# ETH_PCIE_PHY.net
KiCad netlist of a schematic drawn in Altium Designer
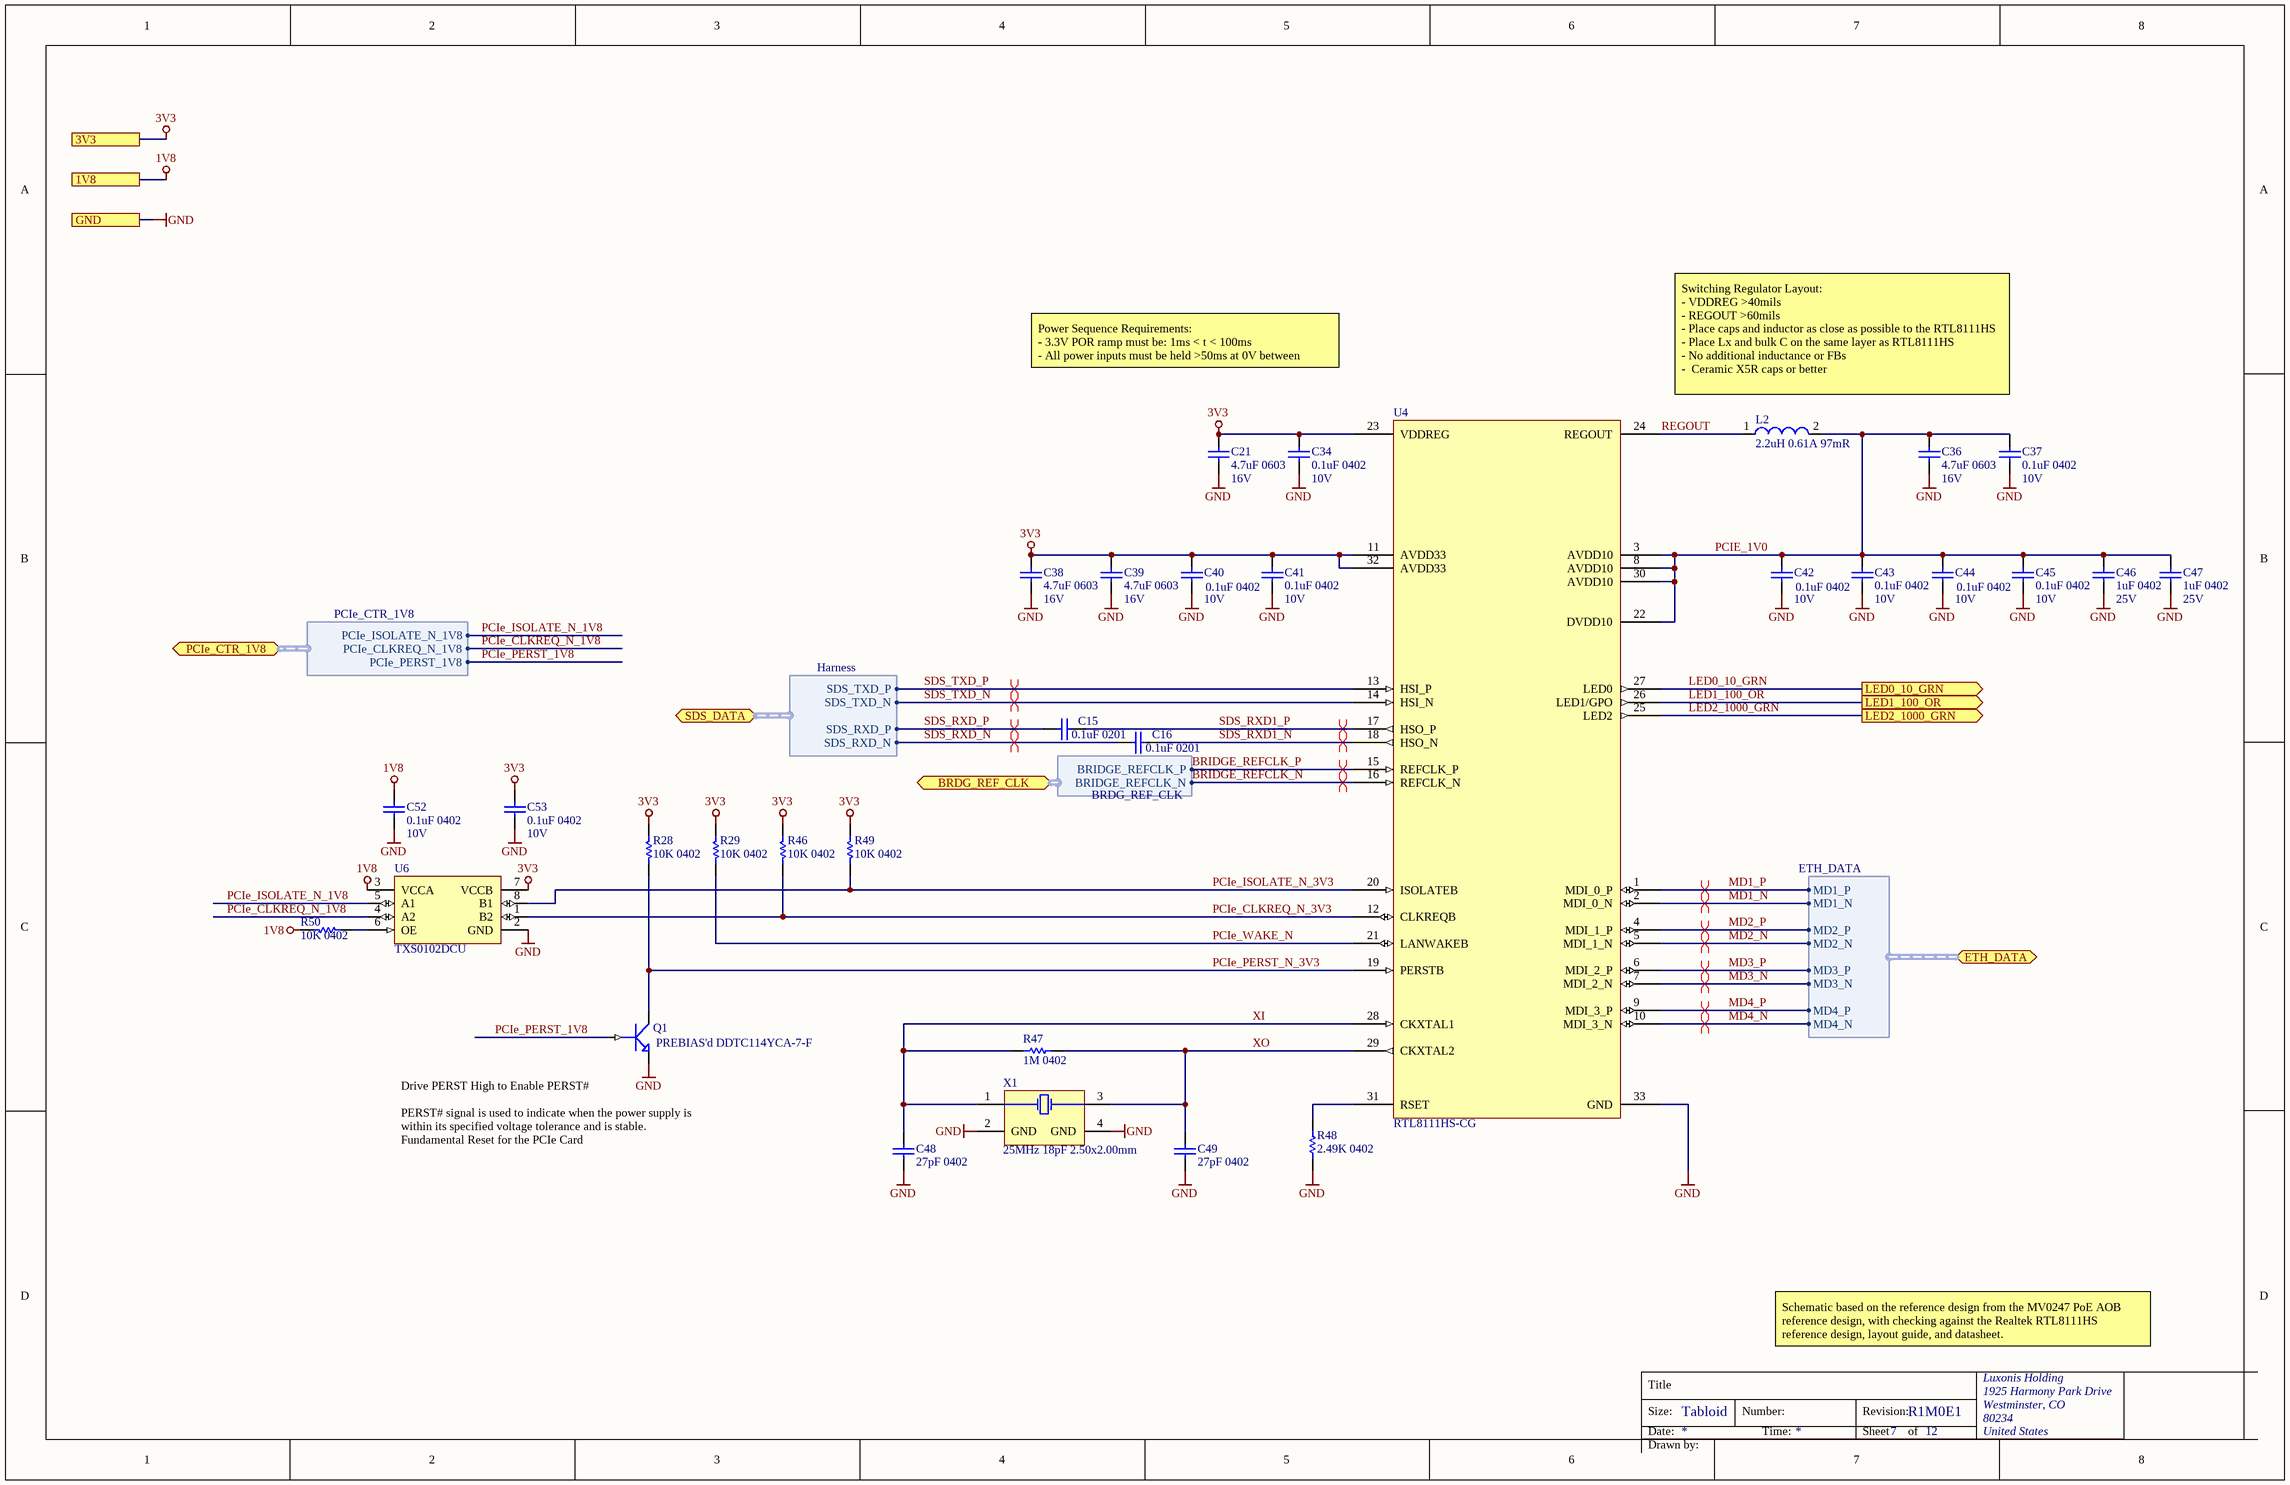
[diagram p0: ETH_PCIE_PHY.SchDoc]

(export (version "E")
  (design (tool "Eeschema 10.0.6"))
  (components
    (comp (ref "C15")
      (value "0.1uF 0201")
      (footprint "CAP_Altium_Vault_Generic:CAPC0201(0603)33_L")
      (description "CAP CER 0.1UF 10V X5R 0201")
      (fields (field (name "TOLERANCE") "10%") (field (name "VOLTAGE") "10V"))
      (libsource (lib "LuxonisMaster") (part "GRM033R61A104KE15D"))
    )
    (comp (ref "C16")
      (value "0.1uF 0201")
      (footprint "CAP_Altium_Vault_Generic:CAPC0201(0603)33_L")
      (description "CAP CER 0.1UF 10V X5R 0201")
      (fields (field (name "TOLERANCE") "10%") (field (name "VOLTAGE") "10V"))
      (libsource (lib "LuxonisMaster") (part "GRM033R61A104KE15D"))
    )
    (comp (ref "C21")
      (value "4.7uF 0603")
      (footprint "CAP_Altium_Vault_Generic:CAPC0603(1608)100_N")
      (description "CAP CER 4.7UF 16V X5R 0603 10%")
      (fields (field (name "TOLERANCE") "10%") (field (name "VOLTAGE RATING") "16V"))
      (libsource (lib "LuxonisMaster") (part "GRM188R61C475KAAJD"))
    )
    (comp (ref "C34")
      (value "0.1uF 0402")
      (footprint "CAP_Altium_Vault_Generic:CAPC0402(1005)70_N")
      (description "CAP CER 0.1UF 10V X7R 0402 5%")
      (fields (field (name "TOLERANCE") "5%") (field (name "VOLTAGE RATING") "10V"))
      (libsource (lib "LuxonisMaster") (part "GRM155R71A104JA01D"))
    )
    (comp (ref "C36")
      (value "4.7uF 0603")
      (footprint "CAP_Altium_Vault_Generic:CAPC0603(1608)100_N")
      (description "CAP CER 4.7UF 16V X5R 0603 10%")
      (fields (field (name "TOLERANCE") "10%") (field (name "VOLTAGE RATING") "16V"))
      (libsource (lib "LuxonisMaster") (part "GRM188R61C475KAAJD"))
    )
    (comp (ref "C37")
      (value "0.1uF 0402")
      (footprint "CAP_Altium_Vault_Generic:CAPC0402(1005)70_N")
      (description "CAP CER 0.1UF 10V X7R 0402 5%")
      (fields (field (name "TOLERANCE") "5%") (field (name "VOLTAGE RATING") "10V"))
      (libsource (lib "LuxonisMaster") (part "GRM155R71A104JA01D"))
    )
    (comp (ref "C38")
      (value "4.7uF 0603")
      (footprint "CAP_Altium_Vault_Generic:CAPC0603(1608)100_N")
      (description "CAP CER 4.7UF 16V X5R 0603 10%")
      (fields (field (name "TOLERANCE") "10%") (field (name "VOLTAGE RATING") "16V"))
      (libsource (lib "LuxonisMaster") (part "GRM188R61C475KAAJD"))
    )
    (comp (ref "C39")
      (value "4.7uF 0603")
      (footprint "CAP_Altium_Vault_Generic:CAPC0603(1608)100_N")
      (description "CAP CER 4.7UF 16V X5R 0603 10%")
      (fields (field (name "TOLERANCE") "10%") (field (name "VOLTAGE RATING") "16V"))
      (libsource (lib "LuxonisMaster") (part "GRM188R61C475KAAJD"))
    )
    (comp (ref "C40")
      (value "0.1uF 0402")
      (footprint "CAP_Altium_Vault_Generic:CAPC0402(1005)70_N")
      (description "CAP CER 0.1UF 10V X7R 0402 5%")
      (fields (field (name "TOLERANCE") "5%") (field (name "VOLTAGE RATING") "10V"))
      (libsource (lib "LuxonisMaster") (part "GRM155R71A104JA01D"))
    )
    (comp (ref "C41")
      (value "0.1uF 0402")
      (footprint "CAP_Altium_Vault_Generic:CAPC0402(1005)70_N")
      (description "CAP CER 0.1UF 10V X7R 0402 5%")
      (fields (field (name "TOLERANCE") "5%") (field (name "VOLTAGE RATING") "10V"))
      (libsource (lib "LuxonisMaster") (part "GRM155R71A104JA01D"))
    )
    (comp (ref "C42")
      (value "0.1uF 0402")
      (footprint "CAP_Altium_Vault_Generic:CAPC0402(1005)70_N")
      (description "CAP CER 0.1UF 10V X7R 0402 5%")
      (fields (field (name "TOLERANCE") "5%") (field (name "VOLTAGE RATING") "10V"))
      (libsource (lib "LuxonisMaster") (part "GRM155R71A104JA01D"))
    )
    (comp (ref "C43")
      (value "0.1uF 0402")
      (footprint "CAP_Altium_Vault_Generic:CAPC0402(1005)70_N")
      (description "CAP CER 0.1UF 10V X7R 0402 5%")
      (fields (field (name "TOLERANCE") "5%") (field (name "VOLTAGE RATING") "10V"))
      (libsource (lib "LuxonisMaster") (part "GRM155R71A104JA01D"))
    )
    (comp (ref "C44")
      (value "0.1uF 0402")
      (footprint "CAP_Altium_Vault_Generic:CAPC0402(1005)70_N")
      (description "CAP CER 0.1UF 10V X7R 0402 5%")
      (fields (field (name "TOLERANCE") "5%") (field (name "VOLTAGE RATING") "10V"))
      (libsource (lib "LuxonisMaster") (part "GRM155R71A104JA01D"))
    )
    (comp (ref "C45")
      (value "0.1uF 0402")
      (footprint "CAP_Altium_Vault_Generic:CAPC0402(1005)70_N")
      (description "CAP CER 0.1UF 10V X7R 0402 5%")
      (fields (field (name "TOLERANCE") "5%") (field (name "VOLTAGE RATING") "10V"))
      (libsource (lib "LuxonisMaster") (part "GRM155R71A104JA01D"))
    )
    (comp (ref "C46")
      (value "1uF 0402")
      (footprint "CAP_Altium_Vault_Generic:CAPC0402(1005)70_N")
      (description "CAP CER 1UF 25V X5R 0402 10%")
      (fields
        (field (name "TOLERANCE") "10%")
        (field (name "VOLTAGE") "25V")
        (field (name "VOLTAGE RATING") "25V")
      )
      (libsource (lib "LuxonisMaster") (part "GRM155R61E105KA12D"))
    )
    (comp (ref "C47")
      (value "1uF 0402")
      (footprint "CAP_Altium_Vault_Generic:CAPC0402(1005)70_N")
      (description "CAP CER 1UF 25V X5R 0402 10%")
      (fields
        (field (name "TOLERANCE") "10%")
        (field (name "VOLTAGE") "25V")
        (field (name "VOLTAGE RATING") "25V")
      )
      (libsource (lib "LuxonisMaster") (part "GRM155R61E105KA12D"))
    )
    (comp (ref "C48")
      (value "27pF 0402")
      (footprint "CAP_Altium_Vault_Generic:CAPC0402(1005)60_N")
      (description "CAP CER 27PF 50V C0G/NP0 0402")
      (fields (field (name "TOLERANCE") "5%") (field (name "VOLTAGE") "50V"))
      (libsource (lib "BW2098POE") (part "C0402C270J5GACTU"))
    )
    (comp (ref "C49")
      (value "27pF 0402")
      (footprint "CAP_Altium_Vault_Generic:CAPC0402(1005)60_N")
      (description "CAP CER 27PF 50V C0G/NP0 0402")
      (fields (field (name "TOLERANCE") "5%") (field (name "VOLTAGE") "50V"))
      (libsource (lib "BW2098POE") (part "C0402C270J5GACTU"))
    )
    (comp (ref "C52")
      (value "0.1uF 0402")
      (footprint "CAP_Altium_Vault_Generic:CAPC0402(1005)70_N")
      (description "CAP CER 0.1UF 10V X7R 0402 5%")
      (fields (field (name "TOLERANCE") "5%") (field (name "VOLTAGE RATING") "10V"))
      (libsource (lib "LuxonisMaster") (part "GRM155R71A104JA01D"))
    )
    (comp (ref "C53")
      (value "0.1uF 0402")
      (footprint "CAP_Altium_Vault_Generic:CAPC0402(1005)70_N")
      (description "CAP CER 0.1UF 10V X7R 0402 5%")
      (fields (field (name "TOLERANCE") "5%") (field (name "VOLTAGE RATING") "10V"))
      (libsource (lib "LuxonisMaster") (part "GRM155R71A104JA01D"))
    )
    (comp (ref "L2")
      (value "2.2uH 0.61A 97mR")
      (footprint "BW2098POE:LQH32NH2R2J23L")
      (description "FIXED IND 2.2UH 610MA 97MOHM SMD")
      (fields (field (name "TOLERANCE") "5%"))
      (libsource (lib "BW2098POE") (part "LQH32NH2R2J23L"))
    )
    (comp (ref "Q1")
      (value "PREBIAS'd DDTC114YCA-7-F")
      (footprint "BW2098POE:DDTC114YCA-7-F")
      (description "TRANS PREBIAS NPN 200MW SOT23-3")
      (libsource (lib "BW2098POE") (part "DDTC114YCA-7-F"))
    )
    (comp (ref "R28")
      (value "10K 0402")
      (footprint "RES_Altium_Vault_Generic:RESC0402(1005)_N")
      (fields (field (name "TOLERANCE") "1%"))
      (libsource (lib "LuxonisMaster") (part "RC0402FR-1310KL"))
    )
    (comp (ref "R29")
      (value "10K 0402")
      (footprint "RES_Altium_Vault_Generic:RESC0402(1005)_N")
      (fields (field (name "TOLERANCE") "1%"))
      (libsource (lib "LuxonisMaster") (part "RC0402FR-1310KL"))
    )
    (comp (ref "R46")
      (value "10K 0402")
      (footprint "RES_Altium_Vault_Generic:RESC0402(1005)_N")
      (fields (field (name "TOLERANCE") "1%"))
      (libsource (lib "LuxonisMaster") (part "RC0402FR-1310KL"))
    )
    (comp (ref "R47")
      (value "1M 0402")
      (footprint "RES_Altium_Vault_Generic:RESC0402(1005)_N")
      (description "RES SMD 1M OHM 1% 1/16W 0402")
      (fields (field (name "TOLERANCE") "1%"))
      (libsource (lib "LuxonisMaster") (part "RC0402FR-071ML"))
    )
    (comp (ref "R48")
      (value "2.49K 0402")
      (footprint "RES_Altium_Vault_Generic:RESC0402(1005)_N")
      (description "RES SMD 2.49K OHM 1% 1/16W 0402")
      (fields (field (name "TOLERANCE") "1%"))
      (libsource (lib "BW2098POE") (part "RC0402FR-072K49L"))
    )
    (comp (ref "R49")
      (value "10K 0402")
      (footprint "RES_Altium_Vault_Generic:RESC0402(1005)_N")
      (fields (field (name "TOLERANCE") "1%"))
      (libsource (lib "LuxonisMaster") (part "RC0402FR-1310KL"))
    )
    (comp (ref "R50")
      (value "10K 0402")
      (footprint "RES_Altium_Vault_Generic:RESC0402(1005)_N")
      (fields (field (name "TOLERANCE") "1%"))
      (libsource (lib "LuxonisMaster") (part "RC0402FR-1310KL"))
    )
    (comp (ref "U4")
      (value "RTL8111HS-CG")
      (footprint "BW2098POE:RTL8111Hx-CG")
      (description "IC ETHERNET/PCIe PHY Realtek")
      (libsource (lib "BW2098POE") (part "RTL8111HS"))
    )
    (comp (ref "U6")
      (value "TXS0102DCU")
      (footprint "BW2098POE:TXS0102DCUR")
      (description "TEXAS INSTRUMENTS - TXS0102DCUR - IC, TRANSLATOR, 2 BIT, BI, US-8")
      (libsource (lib "BW2098POE") (part "TXS0102DCUR"))
    )
    (comp (ref "X1")
      (value "25MHz 18pF 2.50x2.00mm")
      (footprint "BW2098POE:ECS-250-18-36B-CKY-TR")
      (description "CRYSTAL 25.0000MHZ 18PF SMD 25MHz ±10ppm Crystal 18pF 50 Ohms 4-SMD, No Lead")
      (libsource (lib "BW2098POE") (part "ECS-250-18-36B-CKY-TR"))
    )
  )
  (nets
    (net (code "5") (name "/BRIDGE_REFCLK_N") (class "Default")
      (node (ref "U4") (pin "16") (pinfunction "REFCLK_N_16") (pintype "input"))
    )
    (net (code "6") (name "/BRIDGE_REFCLK_P") (class "Default")
      (node (ref "U4") (pin "15") (pinfunction "REFCLK_P_15") (pintype "input"))
    )
    (net (code "7") (name "/LED0_10_GRN") (class "Default")
      (node (ref "U4") (pin "27") (pinfunction "LED0_27") (pintype "output"))
    )
    (net (code "8") (name "/LED1_100_OR") (class "Default")
      (node (ref "U4") (pin "26") (pinfunction "LED1/GPO_26") (pintype "output"))
    )
    (net (code "9") (name "/LED2_1000_GRN") (class "Default")
      (node (ref "U4") (pin "25") (pinfunction "LED2_25") (pintype "output"))
    )
    (net (code "10") (name "/MD1_N") (class "Default")
      (node (ref "U4") (pin "2") (pinfunction "MDI_0_N_2") (pintype "bidirectional"))
    )
    (net (code "11") (name "/MD1_P") (class "Default")
      (node (ref "U4") (pin "1") (pinfunction "MDI_0_P_1") (pintype "bidirectional"))
    )
    (net (code "12") (name "/MD2_N") (class "Default")
      (node (ref "U4") (pin "5") (pinfunction "MDI_1_N_5") (pintype "bidirectional"))
    )
    (net (code "13") (name "/MD2_P") (class "Default")
      (node (ref "U4") (pin "4") (pinfunction "MDI_1_P_4") (pintype "bidirectional"))
    )
    (net (code "14") (name "/MD3_N") (class "Default")
      (node (ref "U4") (pin "7") (pinfunction "MDI_2_N_7") (pintype "bidirectional"))
    )
    (net (code "15") (name "/MD3_P") (class "Default")
      (node (ref "U4") (pin "6") (pinfunction "MDI_2_P_6") (pintype "bidirectional"))
    )
    (net (code "16") (name "/MD4_N") (class "Default")
      (node (ref "U4") (pin "10") (pinfunction "MDI_3_N_10") (pintype "bidirectional"))
    )
    (net (code "17") (name "/MD4_P") (class "Default")
      (node (ref "U4") (pin "9") (pinfunction "MDI_3_P_9") (pintype "bidirectional"))
    )
    (net (code "18") (name "/PCIE_1V0") (class "Default")
      (node (ref "C36") (pin "2") (pinfunction "2_2") (pintype "passive"))
      (node (ref "C37") (pin "2") (pinfunction "2_2") (pintype "passive"))
      (node (ref "C42") (pin "2") (pinfunction "2_2") (pintype "passive"))
      (node (ref "C43") (pin "2") (pinfunction "2_2") (pintype "passive"))
      (node (ref "C44") (pin "2") (pinfunction "2_2") (pintype "passive"))
      (node (ref "C45") (pin "2") (pinfunction "2_2") (pintype "passive"))
      (node (ref "C46") (pin "2") (pinfunction "2_2") (pintype "passive"))
      (node (ref "C47") (pin "2") (pinfunction "2_2") (pintype "passive"))
      (node (ref "L2") (pin "2") (pinfunction "2_2") (pintype "passive"))
      (node (ref "U4") (pin "22") (pinfunction "DVDD10_22") (pintype "passive"))
      (node (ref "U4") (pin "3") (pinfunction "AVDD10_3") (pintype "passive"))
      (node (ref "U4") (pin "30") (pinfunction "AVDD10_30") (pintype "passive"))
      (node (ref "U4") (pin "8") (pinfunction "AVDD10_8") (pintype "passive"))
    )
    (net (code "19") (name "/PCIe_CLKREQ_N_1V8") (class "Default")
      (node (ref "U6") (pin "4") (pinfunction "A2_4") (pintype "bidirectional"))
    )
    (net (code "20") (name "/PCIe_CLKREQ_N_3V3") (class "Default")
      (node (ref "R46") (pin "2") (pinfunction "2_2") (pintype "passive"))
      (node (ref "U4") (pin "12") (pinfunction "CLKREQB_12") (pintype "bidirectional"))
      (node (ref "U6") (pin "1") (pinfunction "B2_1") (pintype "bidirectional"))
    )
    (net (code "21") (name "/PCIe_ISOLATE_N_1V8") (class "Default")
      (node (ref "U6") (pin "5") (pinfunction "A1_5") (pintype "bidirectional"))
    )
    (net (code "22") (name "/PCIe_ISOLATE_N_3V3") (class "Default")
      (node (ref "R49") (pin "2") (pinfunction "2_2") (pintype "passive"))
      (node (ref "U4") (pin "20") (pinfunction "ISOLATEB_20") (pintype "input"))
      (node (ref "U6") (pin "8") (pinfunction "B1_8") (pintype "bidirectional"))
    )
    (net (code "23") (name "/PCIe_PERST_1V8") (class "Default")
      (node (ref "Q1") (pin "1") (pinfunction "B_1") (pintype "input"))
    )
    (net (code "24") (name "/PCIe_PERST_N_3V3") (class "Default")
      (node (ref "Q1") (pin "3") (pinfunction "C_3") (pintype "passive"))
      (node (ref "R28") (pin "2") (pinfunction "2_2") (pintype "passive"))
      (node (ref "U4") (pin "19") (pinfunction "PERSTB_19") (pintype "input"))
    )
    (net (code "25") (name "/PCIe_WAKE_N") (class "Default")
      (node (ref "R29") (pin "2") (pinfunction "2_2") (pintype "passive"))
      (node (ref "U4") (pin "21") (pinfunction "LANWAKEB_21") (pintype "bidirectional"))
    )
    (net (code "26") (name "/REGOUT") (class "Default")
      (node (ref "L2") (pin "1") (pinfunction "1_1") (pintype "passive"))
      (node (ref "U4") (pin "24") (pinfunction "REGOUT_24") (pintype "passive"))
    )
    (net (code "27") (name "/SDS_RXD1_N") (class "Default")
      (node (ref "C16") (pin "2") (pinfunction "2_2") (pintype "passive"))
      (node (ref "U4") (pin "18") (pinfunction "HSO_N_18") (pintype "output"))
    )
    (net (code "28") (name "/SDS_RXD1_P") (class "Default")
      (node (ref "C15") (pin "2") (pinfunction "2_2") (pintype "passive"))
      (node (ref "U4") (pin "17") (pinfunction "HSO_P_17") (pintype "output"))
    )
    (net (code "29") (name "/SDS_RXD_N") (class "Default")
      (node (ref "C16") (pin "1") (pinfunction "1_1") (pintype "passive"))
    )
    (net (code "30") (name "/SDS_RXD_P") (class "Default")
      (node (ref "C15") (pin "1") (pinfunction "1_1") (pintype "passive"))
    )
    (net (code "31") (name "/SDS_TXD_N") (class "Default")
      (node (ref "U4") (pin "14") (pinfunction "HSI_N_14") (pintype "input"))
    )
    (net (code "32") (name "/SDS_TXD_P") (class "Default")
      (node (ref "U4") (pin "13") (pinfunction "HSI_P_13") (pintype "input"))
    )
    (net (code "33") (name "/XI") (class "Default")
      (node (ref "C48") (pin "2") (pinfunction "2_2") (pintype "passive"))
      (node (ref "R47") (pin "1") (pinfunction "1_1") (pintype "passive"))
      (node (ref "U4") (pin "28") (pinfunction "CKXTAL1_28") (pintype "input"))
      (node (ref "X1") (pin "1") (pinfunction "X1_1") (pintype "passive"))
    )
    (net (code "34") (name "/XO") (class "Default")
      (node (ref "C49") (pin "2") (pinfunction "2_2") (pintype "passive"))
      (node (ref "R47") (pin "2") (pinfunction "2_2") (pintype "passive"))
      (node (ref "U4") (pin "29") (pinfunction "CKXTAL2_29") (pintype "output"))
      (node (ref "X1") (pin "3") (pinfunction "X2_3") (pintype "passive"))
    )
    (net (code "39") (name "1V8") (class "Default")
      (node (ref "C52") (pin "2") (pinfunction "2_2") (pintype "passive"))
      (node (ref "R50") (pin "2") (pinfunction "2_2") (pintype "passive"))
      (node (ref "U6") (pin "3") (pinfunction "VCCA_3") (pintype "power_in"))
    )
    (net (code "40") (name "3V3") (class "Default")
      (node (ref "C21") (pin "2") (pinfunction "2_2") (pintype "passive"))
      (node (ref "C34") (pin "2") (pinfunction "2_2") (pintype "passive"))
      (node (ref "C38") (pin "2") (pinfunction "2_2") (pintype "passive"))
      (node (ref "C39") (pin "2") (pinfunction "2_2") (pintype "passive"))
      (node (ref "C40") (pin "2") (pinfunction "2_2") (pintype "passive"))
      (node (ref "C41") (pin "2") (pinfunction "2_2") (pintype "passive"))
      (node (ref "C53") (pin "2") (pinfunction "2_2") (pintype "passive"))
      (node (ref "R28") (pin "1") (pinfunction "1_1") (pintype "passive"))
      (node (ref "R29") (pin "1") (pinfunction "1_1") (pintype "passive"))
      (node (ref "R46") (pin "1") (pinfunction "1_1") (pintype "passive"))
      (node (ref "R49") (pin "1") (pinfunction "1_1") (pintype "passive"))
      (node (ref "U4") (pin "11") (pinfunction "AVDD33_11") (pintype "passive"))
      (node (ref "U4") (pin "23") (pinfunction "VDDREG_23") (pintype "passive"))
      (node (ref "U4") (pin "32") (pinfunction "AVDD33_32") (pintype "passive"))
      (node (ref "U6") (pin "7") (pinfunction "VCCB_7") (pintype "power_in"))
    )
    (net (code "41") (name "GND") (class "Default")
      (node (ref "C21") (pin "1") (pinfunction "1_1") (pintype "passive"))
      (node (ref "C34") (pin "1") (pinfunction "1_1") (pintype "passive"))
      (node (ref "C36") (pin "1") (pinfunction "1_1") (pintype "passive"))
      (node (ref "C37") (pin "1") (pinfunction "1_1") (pintype "passive"))
      (node (ref "C38") (pin "1") (pinfunction "1_1") (pintype "passive"))
      (node (ref "C39") (pin "1") (pinfunction "1_1") (pintype "passive"))
      (node (ref "C40") (pin "1") (pinfunction "1_1") (pintype "passive"))
      (node (ref "C41") (pin "1") (pinfunction "1_1") (pintype "passive"))
      (node (ref "C42") (pin "1") (pinfunction "1_1") (pintype "passive"))
      (node (ref "C43") (pin "1") (pinfunction "1_1") (pintype "passive"))
      (node (ref "C44") (pin "1") (pinfunction "1_1") (pintype "passive"))
      (node (ref "C45") (pin "1") (pinfunction "1_1") (pintype "passive"))
      (node (ref "C46") (pin "1") (pinfunction "1_1") (pintype "passive"))
      (node (ref "C47") (pin "1") (pinfunction "1_1") (pintype "passive"))
      (node (ref "C48") (pin "1") (pinfunction "1_1") (pintype "passive"))
      (node (ref "C49") (pin "1") (pinfunction "1_1") (pintype "passive"))
      (node (ref "C52") (pin "1") (pinfunction "1_1") (pintype "passive"))
      (node (ref "C53") (pin "1") (pinfunction "1_1") (pintype "passive"))
      (node (ref "Q1") (pin "2") (pinfunction "E_2") (pintype "passive"))
      (node (ref "R48") (pin "1") (pinfunction "1_1") (pintype "passive"))
      (node (ref "U4") (pin "33") (pinfunction "GND_33") (pintype "passive"))
      (node (ref "U6") (pin "2") (pinfunction "GND_2") (pintype "power_in"))
      (node (ref "X1") (pin "2") (pinfunction "GND_2") (pintype "power_in"))
      (node (ref "X1") (pin "4") (pinfunction "GND_4") (pintype "power_in"))
    )
    (net (code "42") (name "Net-(U4-RSET)") (class "Default")
      (node (ref "R48") (pin "2") (pinfunction "2_2") (pintype "passive"))
      (node (ref "U4") (pin "31") (pinfunction "RSET_31") (pintype "passive"))
    )
    (net (code "43") (name "Net-(U6-OE)") (class "Default")
      (node (ref "R50") (pin "1") (pinfunction "1_1") (pintype "passive"))
      (node (ref "U6") (pin "6") (pinfunction "OE_6") (pintype "input"))
    )
  )
)
